# JY901.net
KiCad netlist of a schematic drawn in Altium Designer
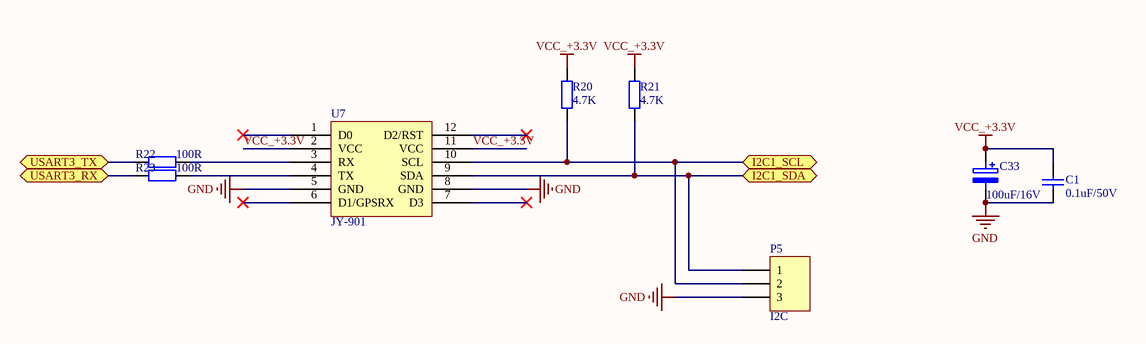
[diagram p0: JY901.SchDoc]

(export (version "E")
  (design (tool "Eeschema 10.0.6"))
  (components
    (comp (ref "C1")
      (value "0.1uF/50V")
      (footprint "0603C")
      (description "Capacitor")
      (fields (field (name "PUBLISHER") "Altium Limited"))
      (libsource (lib "Calf") (part "Cap"))
    )
    (comp (ref "C33")
      (value "100uF/16V")
      (footprint "1206C")
      (description "Electrolytic Capacitor")
      (libsource (lib "Schlib") (part "EC"))
    )
    (comp (ref "P5")
      (value "I2C")
      (footprint "XH254-3P")
      (description "Header, 3-Pin, Right Angle")
      (fields (field (name "PUBLISHER") "Altium Limited"))
      (libsource (lib "Miscellaneous Connectors") (part "Header 3H"))
    )
    (comp (ref "R20") (value "4.7K") (footprint "0603R") (libsource (lib "*") (part "0603R")))
    (comp (ref "R21") (value "4.7K") (footprint "0603R") (libsource (lib "*") (part "0603R")))
    (comp (ref "R22") (value "100R") (footprint "0603R") (libsource (lib "") (part "0603R_1")))
    (comp (ref "R23") (value "100R") (footprint "0603R") (libsource (lib "") (part "0603R_1")))
    (comp (ref "U7")
      (value "JY-901")
      (footprint "JY-901")
      (description "君悦智控高精度9轴传感器")
      (libsource (lib "JYModule") (part "JY-901"))
    )
  )
  (nets
    (net (code "1") (name "/I2C1_SCL") (class "Default")
      (node (ref "P5") (pin "2") (pinfunction "2_2") (pintype "passive"))
      (node (ref "R20") (pin "2") (pinfunction "2_2") (pintype "passive"))
      (node (ref "U7") (pin "10") (pinfunction "SCL_10") (pintype "passive"))
    )
    (net (code "2") (name "/I2C1_SDA") (class "Default")
      (node (ref "P5") (pin "1") (pinfunction "1_1") (pintype "passive"))
      (node (ref "R21") (pin "2") (pinfunction "2_2") (pintype "passive"))
      (node (ref "U7") (pin "9") (pinfunction "SDA_9") (pintype "passive"))
    )
    (net (code "3") (name "/USART3_RX") (class "Default")
      (node (ref "R23") (pin "1") (pinfunction "1_1") (pintype "passive"))
    )
    (net (code "4") (name "/USART3_TX") (class "Default")
      (node (ref "R22") (pin "1") (pinfunction "1_1") (pintype "passive"))
    )
    (net (code "5") (name "GND") (class "Default")
      (node (ref "C1") (pin "1") (pinfunction "1_1") (pintype "passive"))
      (node (ref "C33") (pin "2") (pinfunction "2_2") (pintype "passive"))
      (node (ref "P5") (pin "3") (pinfunction "3_3") (pintype "passive"))
      (node (ref "U7") (pin "5") (pinfunction "GND_5") (pintype "passive"))
      (node (ref "U7") (pin "8") (pinfunction "GND_8") (pintype "passive"))
    )
    (net (code "6") (name "Net-(U7-RX)") (class "Default")
      (node (ref "R22") (pin "2") (pinfunction "2_2") (pintype "passive"))
      (node (ref "U7") (pin "3") (pinfunction "RX_3") (pintype "passive"))
    )
    (net (code "7") (name "Net-(U7-TX)") (class "Default")
      (node (ref "R23") (pin "2") (pinfunction "2_2") (pintype "passive"))
      (node (ref "U7") (pin "4") (pinfunction "TX_4") (pintype "passive"))
    )
    (net (code "8") (name "VCC_+3.3V") (class "Default")
      (node (ref "C1") (pin "2") (pinfunction "2_2") (pintype "passive"))
      (node (ref "C33") (pin "1") (pinfunction "1_1") (pintype "passive"))
      (node (ref "R20") (pin "1") (pinfunction "1_1") (pintype "passive"))
      (node (ref "R21") (pin "1") (pinfunction "1_1") (pintype "passive"))
      (node (ref "U7") (pin "11") (pinfunction "VCC_11") (pintype "passive"))
      (node (ref "U7") (pin "2") (pinfunction "VCC_2") (pintype "passive"))
    )
    (net (code "9") (name "unconnected-(U7-D0-Pad1)") (class "Default")
      (node (ref "U7") (pin "1") (pinfunction "D0_1") (pintype "passive+no_connect"))
    )
    (net (code "10") (name "unconnected-(U7-D1{slash}GPSRX-Pad6)") (class "Default")
      (node (ref "U7") (pin "6") (pinfunction "D1/GPSRX_6") (pintype "passive+no_connect"))
    )
    (net (code "11") (name "unconnected-(U7-D2{slash}RST-Pad12)") (class "Default")
      (node (ref "U7") (pin "12") (pinfunction "D2/RST_12") (pintype "passive+no_connect"))
    )
    (net (code "12") (name "unconnected-(U7-D3-Pad7)") (class "Default")
      (node (ref "U7") (pin "7") (pinfunction "D3_7") (pintype "passive+no_connect"))
    )
  )
)
